# main.net
KiCad netlist of a schematic drawn in EAGLE
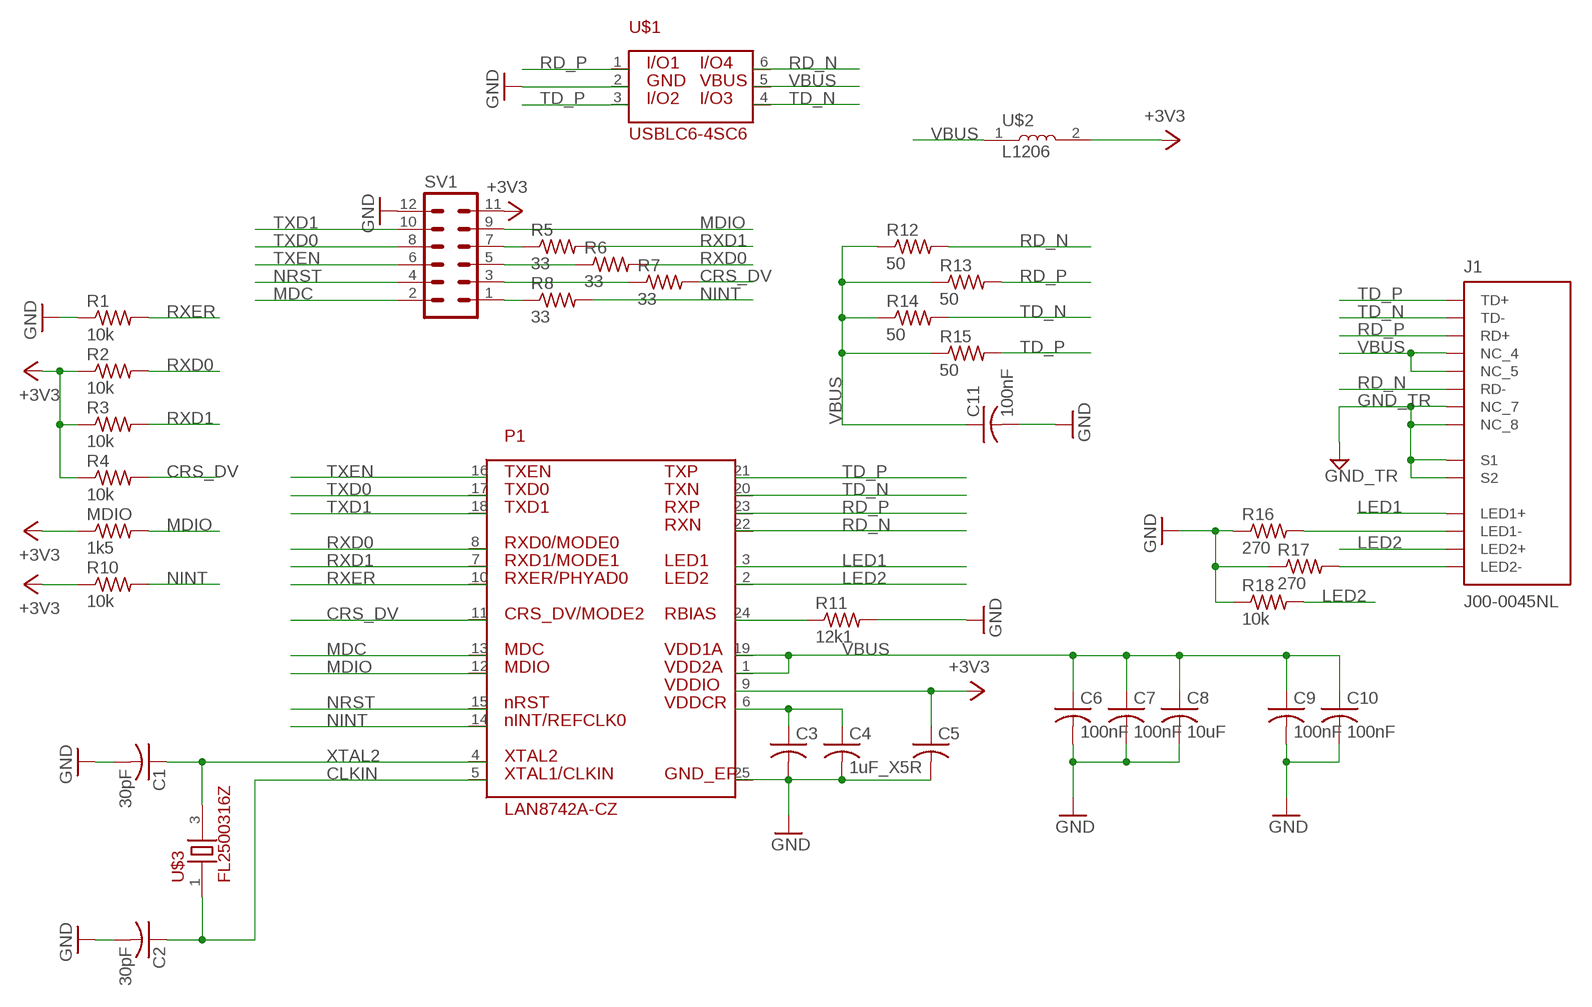
[diagram p0: schematic, sheet 1]

(export (version "E")
  (design (tool "Eeschema 10.0.6"))
  (components
    (comp (ref "C1")
      (value "30pF")
      (footprint "eagle-import:C0603")
      (libsource (lib "eagle-import") (part "C-USC0603"))
    )
    (comp (ref "C2")
      (value "30pF")
      (footprint "eagle-import:C0603")
      (libsource (lib "eagle-import") (part "C-USC0603"))
    )
    (comp (ref "C3")
      (value "C-USC0603")
      (footprint "eagle-import:C0603")
      (libsource (lib "eagle-import") (part "C-USC0603"))
    )
    (comp (ref "C4")
      (value "1uF_X5R")
      (footprint "eagle-import:C0603")
      (libsource (lib "eagle-import") (part "C-USC0603"))
    )
    (comp (ref "C5")
      (value "C-USC0603")
      (footprint "eagle-import:C0603")
      (libsource (lib "eagle-import") (part "C-USC0603"))
    )
    (comp (ref "C6")
      (value "100nF")
      (footprint "eagle-import:C0603")
      (libsource (lib "eagle-import") (part "C-USC0603"))
    )
    (comp (ref "C7")
      (value "100nF")
      (footprint "eagle-import:C0603")
      (libsource (lib "eagle-import") (part "C-USC0603"))
    )
    (comp (ref "C8")
      (value "10uF")
      (footprint "eagle-import:C1206K")
      (libsource (lib "eagle-import") (part "C-USC1206K"))
    )
    (comp (ref "C9")
      (value "100nF")
      (footprint "eagle-import:C0603")
      (libsource (lib "eagle-import") (part "C-USC0603"))
    )
    (comp (ref "C10")
      (value "100nF")
      (footprint "eagle-import:C0603")
      (libsource (lib "eagle-import") (part "C-USC0603"))
    )
    (comp (ref "C11")
      (value "100nF")
      (footprint "eagle-import:C0603")
      (libsource (lib "eagle-import") (part "C-USC0603"))
    )
    (comp (ref "J1")
      (value "J00-0045NL")
      (footprint "eagle-import:PULSE_J00-0045NL")
      (fields (field (name "MF") "Pulse Electronics"))
      (libsource (lib "eagle-import") (part "J00-0045NL"))
    )
    (comp (ref "MDIO")
      (value "1k5")
      (footprint "eagle-import:R0603")
      (libsource (lib "eagle-import") (part "R-US_R0603"))
    )
    (comp (ref "P1")
      (value "LAN8742A-CZ")
      (footprint "eagle-import:LAN8742A-CZ")
      (fields (field (name "MANUFACTURER") "Microchip"))
      (libsource (lib "eagle-import") (part "LAN8742A-CZ"))
    )
    (comp (ref "R1")
      (value "10k")
      (footprint "eagle-import:R0603")
      (libsource (lib "eagle-import") (part "R-US_R0603"))
    )
    (comp (ref "R2")
      (value "10k")
      (footprint "eagle-import:R0603")
      (libsource (lib "eagle-import") (part "R-US_R0603"))
    )
    (comp (ref "R3")
      (value "10k")
      (footprint "eagle-import:R0603")
      (libsource (lib "eagle-import") (part "R-US_R0603"))
    )
    (comp (ref "R4")
      (value "10k")
      (footprint "eagle-import:R0603")
      (libsource (lib "eagle-import") (part "R-US_R0603"))
    )
    (comp (ref "R5")
      (value "33")
      (footprint "eagle-import:R0603")
      (libsource (lib "eagle-import") (part "R-US_R0603"))
    )
    (comp (ref "R6")
      (value "33")
      (footprint "eagle-import:R0603")
      (libsource (lib "eagle-import") (part "R-US_R0603"))
    )
    (comp (ref "R7")
      (value "33")
      (footprint "eagle-import:R0603")
      (libsource (lib "eagle-import") (part "R-US_R0603"))
    )
    (comp (ref "R8")
      (value "33")
      (footprint "eagle-import:R0603")
      (libsource (lib "eagle-import") (part "R-US_R0603"))
    )
    (comp (ref "R10")
      (value "10k")
      (footprint "eagle-import:R0603")
      (libsource (lib "eagle-import") (part "R-US_R0603"))
    )
    (comp (ref "R11")
      (value "12k1")
      (footprint "eagle-import:R0603")
      (libsource (lib "eagle-import") (part "R-US_R0603"))
    )
    (comp (ref "R12")
      (value "50")
      (footprint "eagle-import:R0603")
      (libsource (lib "eagle-import") (part "R-US_R0603"))
    )
    (comp (ref "R13")
      (value "50")
      (footprint "eagle-import:R0603")
      (libsource (lib "eagle-import") (part "R-US_R0603"))
    )
    (comp (ref "R14")
      (value "50")
      (footprint "eagle-import:R0603")
      (libsource (lib "eagle-import") (part "R-US_R0603"))
    )
    (comp (ref "R15")
      (value "50")
      (footprint "eagle-import:R0603")
      (libsource (lib "eagle-import") (part "R-US_R0603"))
    )
    (comp (ref "R16")
      (value "270")
      (footprint "eagle-import:R0603")
      (libsource (lib "eagle-import") (part "R-US_R0603"))
    )
    (comp (ref "R17")
      (value "270")
      (footprint "eagle-import:R0603")
      (libsource (lib "eagle-import") (part "R-US_R0603"))
    )
    (comp (ref "R18")
      (value "10k")
      (footprint "eagle-import:R0603")
      (libsource (lib "eagle-import") (part "R-US_R0603"))
    )
    (comp (ref "SV1")
      (value "MA06-2")
      (footprint "eagle-import:MA06-2")
      (libsource (lib "eagle-import") (part "MA06-2"))
    )
    (comp (ref "U$1")
      (value "USBLC6-4SC6")
      (footprint "eagle-import:SOT95P280X145-6N")
      (libsource (lib "eagle-import") (part "USBLC6-4SC6"))
    )
    (comp (ref "U$2")
      (value "L1206")
      (footprint "eagle-import:RESC3216X125N")
      (libsource (lib "eagle-import") (part "L1206"))
    )
    (comp (ref "U$3")
      (value "FL2500316Z")
      (footprint "eagle-import:FL2500316Z")
      (libsource (lib "eagle-import") (part "FL2500316Z"))
    )
  )
  (nets
    (net (code "1") (name "+3V3") (class "Default")
      (node (ref "C5") (pin "1") (pinfunction "1_1") (pintype "passive"))
      (node (ref "MDIO") (pin "1") (pinfunction "1_1") (pintype "passive"))
      (node (ref "P1") (pin "9") (pinfunction "P$16_9") (pintype "bidirectional"))
      (node (ref "R10") (pin "1") (pinfunction "1_1") (pintype "passive"))
      (node (ref "R2") (pin "1") (pinfunction "1_1") (pintype "passive"))
      (node (ref "R3") (pin "1") (pinfunction "1_1") (pintype "passive"))
      (node (ref "R4") (pin "1") (pinfunction "1_1") (pintype "passive"))
      (node (ref "SV1") (pin "11") (pinfunction "11_11") (pintype "passive"))
      (node (ref "U$2") (pin "2") (pinfunction "2_2") (pintype "passive"))
    )
    (net (code "2") (name "/CLKIN") (class "Default")
      (node (ref "C2") (pin "1") (pinfunction "1_1") (pintype "passive"))
      (node (ref "P1") (pin "5") (pinfunction "P$13_5") (pintype "bidirectional"))
      (node (ref "U$3") (pin "1") (pinfunction "P$1_1") (pintype "bidirectional"))
    )
    (net (code "3") (name "/CRS_DV") (class "Default")
      (node (ref "P1") (pin "11") (pinfunction "P$7_11") (pintype "bidirectional"))
      (node (ref "R4") (pin "2") (pinfunction "2_2") (pintype "passive"))
      (node (ref "R7") (pin "2") (pinfunction "2_2") (pintype "passive"))
    )
    (net (code "4") (name "/LED1") (class "Default")
      (node (ref "J1") (pin "9") (pinfunction "LED1+_9") (pintype "bidirectional"))
      (node (ref "P1") (pin "3") (pinfunction "P$21_3") (pintype "bidirectional"))
    )
    (net (code "5") (name "/LED2") (class "Default")
      (node (ref "J1") (pin "12") (pinfunction "LED2+_12") (pintype "bidirectional"))
      (node (ref "P1") (pin "2") (pinfunction "P$20_2") (pintype "bidirectional"))
      (node (ref "R18") (pin "2") (pinfunction "2_2") (pintype "passive"))
    )
    (net (code "6") (name "/MDC") (class "Default")
      (node (ref "P1") (pin "13") (pinfunction "P$8_13") (pintype "bidirectional"))
      (node (ref "SV1") (pin "2") (pinfunction "2_2") (pintype "passive"))
    )
    (net (code "7") (name "/MDIO") (class "Default")
      (node (ref "MDIO") (pin "2") (pinfunction "2_2") (pintype "passive"))
      (node (ref "P1") (pin "12") (pinfunction "P$9_12") (pintype "bidirectional"))
      (node (ref "SV1") (pin "9") (pinfunction "9_9") (pintype "passive"))
    )
    (net (code "8") (name "/NINT") (class "Default")
      (node (ref "P1") (pin "14") (pinfunction "P$11_14") (pintype "bidirectional"))
      (node (ref "R10") (pin "2") (pinfunction "2_2") (pintype "passive"))
      (node (ref "R8") (pin "2") (pinfunction "2_2") (pintype "passive"))
    )
    (net (code "9") (name "/NRST") (class "Default")
      (node (ref "P1") (pin "15") (pinfunction "P$10_15") (pintype "bidirectional"))
      (node (ref "SV1") (pin "4") (pinfunction "4_4") (pintype "passive"))
    )
    (net (code "10") (name "/RD_N") (class "Default")
      (node (ref "J1") (pin "6") (pinfunction "RD-_6") (pintype "bidirectional"))
      (node (ref "P1") (pin "22") (pinfunction "P$22_22") (pintype "bidirectional"))
      (node (ref "R12") (pin "2") (pinfunction "2_2") (pintype "passive"))
      (node (ref "U$1") (pin "6") (pinfunction "P$6_6") (pintype "bidirectional"))
    )
    (net (code "11") (name "/RD_P") (class "Default")
      (node (ref "J1") (pin "3") (pinfunction "RD+_3") (pintype "bidirectional"))
      (node (ref "P1") (pin "23") (pinfunction "P$23_23") (pintype "bidirectional"))
      (node (ref "R13") (pin "2") (pinfunction "2_2") (pintype "passive"))
      (node (ref "U$1") (pin "1") (pinfunction "P$1_1") (pintype "bidirectional"))
    )
    (net (code "12") (name "/RXD0") (class "Default")
      (node (ref "P1") (pin "8") (pinfunction "P$4_8") (pintype "bidirectional"))
      (node (ref "R2") (pin "2") (pinfunction "2_2") (pintype "passive"))
      (node (ref "R6") (pin "2") (pinfunction "2_2") (pintype "passive"))
    )
    (net (code "13") (name "/RXD1") (class "Default")
      (node (ref "P1") (pin "7") (pinfunction "P$5_7") (pintype "bidirectional"))
      (node (ref "R3") (pin "2") (pinfunction "2_2") (pintype "passive"))
      (node (ref "R5") (pin "2") (pinfunction "2_2") (pintype "passive"))
    )
    (net (code "14") (name "/RXER") (class "Default")
      (node (ref "P1") (pin "10") (pinfunction "P$6_10") (pintype "bidirectional"))
      (node (ref "R1") (pin "2") (pinfunction "2_2") (pintype "passive"))
    )
    (net (code "15") (name "/TD_N") (class "Default")
      (node (ref "J1") (pin "2") (pinfunction "TD-_2") (pintype "bidirectional"))
      (node (ref "P1") (pin "20") (pinfunction "P$24_20") (pintype "bidirectional"))
      (node (ref "R14") (pin "2") (pinfunction "2_2") (pintype "passive"))
      (node (ref "U$1") (pin "4") (pinfunction "P$4_4") (pintype "bidirectional"))
    )
    (net (code "16") (name "/TD_P") (class "Default")
      (node (ref "J1") (pin "1") (pinfunction "TD+_1") (pintype "bidirectional"))
      (node (ref "P1") (pin "21") (pinfunction "P$25_21") (pintype "bidirectional"))
      (node (ref "R15") (pin "2") (pinfunction "2_2") (pintype "passive"))
      (node (ref "U$1") (pin "3") (pinfunction "P$3_3") (pintype "bidirectional"))
    )
    (net (code "17") (name "/TXD0") (class "Default")
      (node (ref "P1") (pin "17") (pinfunction "P$2_17") (pintype "bidirectional"))
      (node (ref "SV1") (pin "8") (pinfunction "8_8") (pintype "passive"))
    )
    (net (code "18") (name "/TXD1") (class "Default")
      (node (ref "P1") (pin "18") (pinfunction "P$3_18") (pintype "bidirectional"))
      (node (ref "SV1") (pin "10") (pinfunction "10_10") (pintype "passive"))
    )
    (net (code "19") (name "/TXEN") (class "Default")
      (node (ref "P1") (pin "16") (pinfunction "P$1_16") (pintype "bidirectional"))
      (node (ref "SV1") (pin "6") (pinfunction "6_6") (pintype "passive"))
    )
    (net (code "20") (name "/VBUS") (class "Default")
      (node (ref "C10") (pin "1") (pinfunction "1_1") (pintype "passive"))
      (node (ref "C11") (pin "1") (pinfunction "1_1") (pintype "passive"))
      (node (ref "C6") (pin "1") (pinfunction "1_1") (pintype "passive"))
      (node (ref "C7") (pin "1") (pinfunction "1_1") (pintype "passive"))
      (node (ref "C8") (pin "1") (pinfunction "1_1") (pintype "passive"))
      (node (ref "C9") (pin "1") (pinfunction "1_1") (pintype "passive"))
      (node (ref "J1") (pin "4") (pinfunction "NC_4_4") (pintype "bidirectional"))
      (node (ref "J1") (pin "5") (pinfunction "NC_5_5") (pintype "bidirectional"))
      (node (ref "P1") (pin "1") (pinfunction "P$17_1") (pintype "bidirectional"))
      (node (ref "P1") (pin "19") (pinfunction "P$18_19") (pintype "bidirectional"))
      (node (ref "R12") (pin "1") (pinfunction "1_1") (pintype "passive"))
      (node (ref "R13") (pin "1") (pinfunction "1_1") (pintype "passive"))
      (node (ref "R14") (pin "1") (pinfunction "1_1") (pintype "passive"))
      (node (ref "R15") (pin "1") (pinfunction "1_1") (pintype "passive"))
      (node (ref "U$1") (pin "5") (pinfunction "P$5_5") (pintype "bidirectional"))
      (node (ref "U$2") (pin "1") (pinfunction "1_1") (pintype "passive"))
    )
    (net (code "21") (name "/XTAL2") (class "Default")
      (node (ref "C1") (pin "1") (pinfunction "1_1") (pintype "passive"))
      (node (ref "P1") (pin "4") (pinfunction "P$12_4") (pintype "bidirectional"))
      (node (ref "U$3") (pin "3") (pinfunction "P$2_3") (pintype "bidirectional"))
    )
    (net (code "22") (name "GND") (class "Default")
      (node (ref "C1") (pin "2") (pinfunction "2_2") (pintype "passive"))
      (node (ref "C10") (pin "2") (pinfunction "2_2") (pintype "passive"))
      (node (ref "C11") (pin "2") (pinfunction "2_2") (pintype "passive"))
      (node (ref "C2") (pin "2") (pinfunction "2_2") (pintype "passive"))
      (node (ref "C3") (pin "2") (pinfunction "2_2") (pintype "passive"))
      (node (ref "C4") (pin "2") (pinfunction "2_2") (pintype "passive"))
      (node (ref "C5") (pin "2") (pinfunction "2_2") (pintype "passive"))
      (node (ref "C6") (pin "2") (pinfunction "2_2") (pintype "passive"))
      (node (ref "C7") (pin "2") (pinfunction "2_2") (pintype "passive"))
      (node (ref "C8") (pin "2") (pinfunction "2_2") (pintype "passive"))
      (node (ref "C9") (pin "2") (pinfunction "2_2") (pintype "passive"))
      (node (ref "P1") (pin "25") (pinfunction "P$14_25") (pintype "bidirectional"))
      (node (ref "R1") (pin "1") (pinfunction "1_1") (pintype "passive"))
      (node (ref "R11") (pin "2") (pinfunction "2_2") (pintype "passive"))
      (node (ref "R16") (pin "1") (pinfunction "1_1") (pintype "passive"))
      (node (ref "R17") (pin "1") (pinfunction "1_1") (pintype "passive"))
      (node (ref "R18") (pin "1") (pinfunction "1_1") (pintype "passive"))
      (node (ref "SV1") (pin "12") (pinfunction "12_12") (pintype "passive"))
      (node (ref "U$1") (pin "2") (pinfunction "P$2_2") (pintype "bidirectional"))
    )
    (net (code "23") (name "GND_TR") (class "Default")
      (node (ref "J1") (pin "7") (pinfunction "NC_7_7") (pintype "bidirectional"))
      (node (ref "J1") (pin "8") (pinfunction "NC_8_8") (pintype "bidirectional"))
      (node (ref "J1") (pin "S1") (pinfunction "S1_S1") (pintype "bidirectional"))
      (node (ref "J1") (pin "S2") (pinfunction "S2_S2") (pintype "bidirectional"))
    )
    (net (code "24") (name "Net-(J1-LED1-)") (class "Default")
      (node (ref "J1") (pin "10") (pinfunction "LED1-_10") (pintype "bidirectional"))
      (node (ref "R16") (pin "2") (pinfunction "2_2") (pintype "passive"))
    )
    (net (code "25") (name "Net-(J1-LED2-)") (class "Default")
      (node (ref "J1") (pin "11") (pinfunction "LED2-_11") (pintype "bidirectional"))
      (node (ref "R17") (pin "2") (pinfunction "2_2") (pintype "passive"))
    )
    (net (code "26") (name "Net-(P1-P$15)") (class "Default")
      (node (ref "C3") (pin "1") (pinfunction "1_1") (pintype "passive"))
      (node (ref "C4") (pin "1") (pinfunction "1_1") (pintype "passive"))
      (node (ref "P1") (pin "6") (pinfunction "P$15_6") (pintype "bidirectional"))
    )
    (net (code "27") (name "Net-(P1-P$19)") (class "Default")
      (node (ref "P1") (pin "24") (pinfunction "P$19_24") (pintype "bidirectional"))
      (node (ref "R11") (pin "1") (pinfunction "1_1") (pintype "passive"))
    )
    (net (code "28") (name "Net-(R5-Pad1)") (class "Default")
      (node (ref "R5") (pin "1") (pinfunction "1_1") (pintype "passive"))
      (node (ref "SV1") (pin "7") (pinfunction "7_7") (pintype "passive"))
    )
    (net (code "29") (name "Net-(R6-Pad1)") (class "Default")
      (node (ref "R6") (pin "1") (pinfunction "1_1") (pintype "passive"))
      (node (ref "SV1") (pin "5") (pinfunction "5_5") (pintype "passive"))
    )
    (net (code "30") (name "Net-(R7-Pad1)") (class "Default")
      (node (ref "R7") (pin "1") (pinfunction "1_1") (pintype "passive"))
      (node (ref "SV1") (pin "3") (pinfunction "3_3") (pintype "passive"))
    )
    (net (code "31") (name "Net-(R8-Pad1)") (class "Default")
      (node (ref "R8") (pin "1") (pinfunction "1_1") (pintype "passive"))
      (node (ref "SV1") (pin "1") (pinfunction "1_1") (pintype "passive"))
    )
  )
)
